# scrap.net
KiCad netlist of a schematic drawn in EAGLE
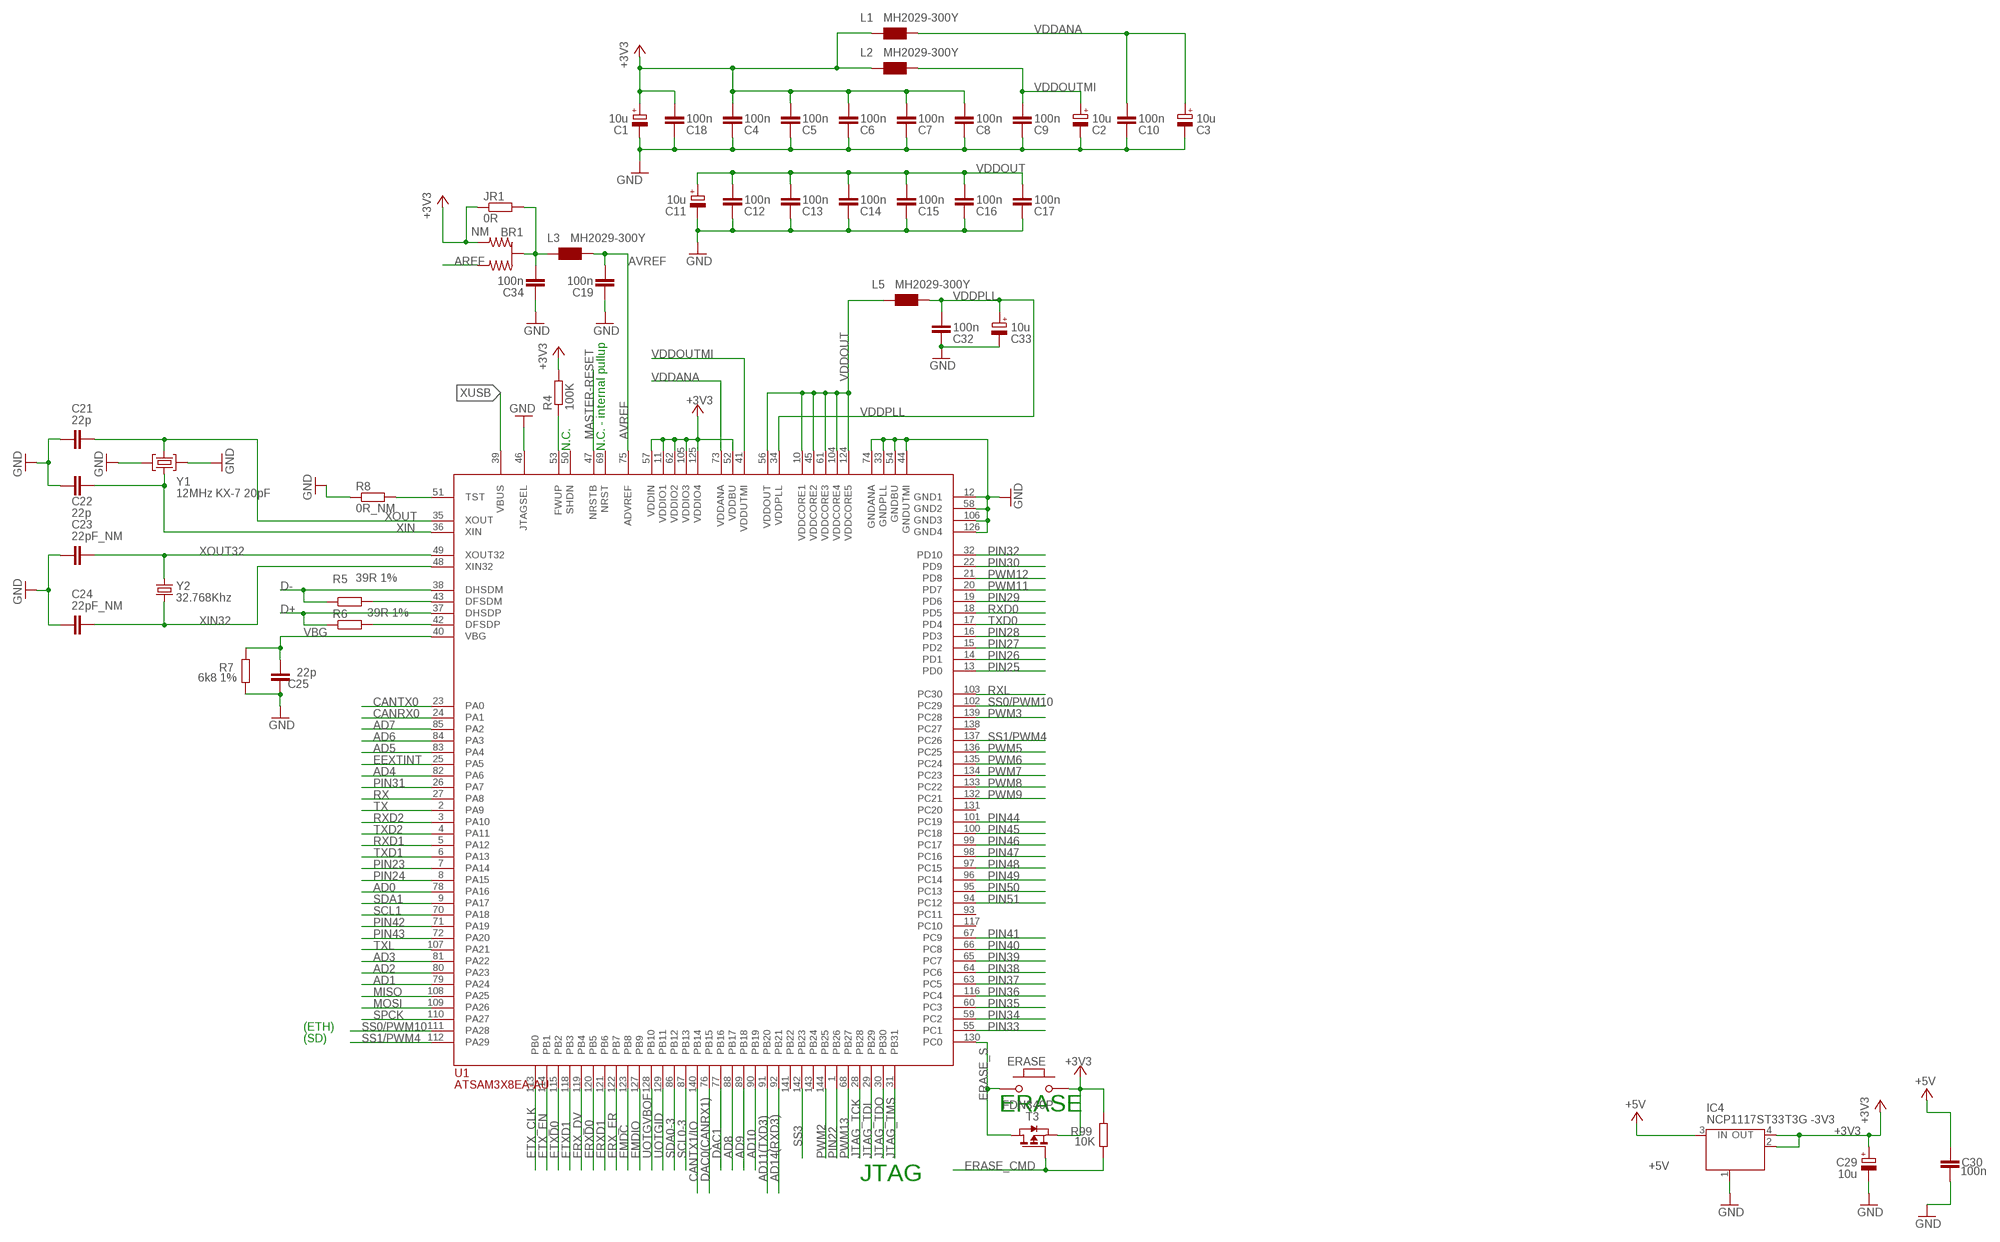
[diagram p0: schematic, sheet 1]

(export (version "E")
  (design (tool "Eeschema 10.0.6"))
  (components
    (comp (ref "BR1")
      (value "NM")
      (footprint "eagle-import:J0402")
      (libsource (lib "eagle-import") (part "J0402"))
    )
    (comp (ref "C1")
      (value "10u")
      (footprint "eagle-import:SMC_B")
      (libsource (lib "eagle-import") (part "CPOL-EUSMCB"))
    )
    (comp (ref "C2")
      (value "10u")
      (footprint "eagle-import:SMC_B")
      (libsource (lib "eagle-import") (part "CPOL-EUSMCB"))
    )
    (comp (ref "C3")
      (value "10u")
      (footprint "eagle-import:SMC_B")
      (libsource (lib "eagle-import") (part "CPOL-EUSMCB"))
    )
    (comp (ref "C4")
      (value "100n")
      (footprint "eagle-import:C0402")
      (libsource (lib "eagle-import") (part "C-EUC0402"))
    )
    (comp (ref "C5")
      (value "100n")
      (footprint "eagle-import:C0402")
      (libsource (lib "eagle-import") (part "C-EUC0402"))
    )
    (comp (ref "C6")
      (value "100n")
      (footprint "eagle-import:C0402")
      (libsource (lib "eagle-import") (part "C-EUC0402"))
    )
    (comp (ref "C7")
      (value "100n")
      (footprint "eagle-import:C0402")
      (libsource (lib "eagle-import") (part "C-EUC0402"))
    )
    (comp (ref "C8")
      (value "100n")
      (footprint "eagle-import:C0402")
      (libsource (lib "eagle-import") (part "C-EUC0402"))
    )
    (comp (ref "C9")
      (value "100n")
      (footprint "eagle-import:C0402")
      (libsource (lib "eagle-import") (part "C-EUC0402"))
    )
    (comp (ref "C10")
      (value "100n")
      (footprint "eagle-import:C0402")
      (libsource (lib "eagle-import") (part "C-EUC0402"))
    )
    (comp (ref "C11")
      (value "10u")
      (footprint "eagle-import:SMC_B")
      (libsource (lib "eagle-import") (part "CPOL-EUSMCB"))
    )
    (comp (ref "C12")
      (value "100n")
      (footprint "eagle-import:C0402")
      (libsource (lib "eagle-import") (part "C-EUC0402"))
    )
    (comp (ref "C13")
      (value "100n")
      (footprint "eagle-import:C0402")
      (libsource (lib "eagle-import") (part "C-EUC0402"))
    )
    (comp (ref "C14")
      (value "100n")
      (footprint "eagle-import:C0402")
      (libsource (lib "eagle-import") (part "C-EUC0402"))
    )
    (comp (ref "C15")
      (value "100n")
      (footprint "eagle-import:C0402")
      (libsource (lib "eagle-import") (part "C-EUC0402"))
    )
    (comp (ref "C16")
      (value "100n")
      (footprint "eagle-import:C0402")
      (libsource (lib "eagle-import") (part "C-EUC0402"))
    )
    (comp (ref "C17")
      (value "100n")
      (footprint "eagle-import:C0402")
      (libsource (lib "eagle-import") (part "C-EUC0402"))
    )
    (comp (ref "C18")
      (value "100n")
      (footprint "eagle-import:C0402")
      (libsource (lib "eagle-import") (part "C-EUC0402"))
    )
    (comp (ref "C19")
      (value "100n")
      (footprint "eagle-import:C0402")
      (libsource (lib "eagle-import") (part "C-EUC0402"))
    )
    (comp (ref "C21")
      (value "22p")
      (footprint "eagle-import:C0402")
      (libsource (lib "eagle-import") (part "C-EUC0402"))
    )
    (comp (ref "C22")
      (value "22p")
      (footprint "eagle-import:C0402")
      (libsource (lib "eagle-import") (part "C-EUC0402"))
    )
    (comp (ref "C23")
      (value "22pF_NM")
      (footprint "eagle-import:C0402")
      (libsource (lib "eagle-import") (part "C-EUC0402"))
    )
    (comp (ref "C24")
      (value "22pF_NM")
      (footprint "eagle-import:C0402")
      (libsource (lib "eagle-import") (part "C-EUC0402"))
    )
    (comp (ref "C25")
      (value "22p")
      (footprint "eagle-import:C0402")
      (libsource (lib "eagle-import") (part "C-EUC0402"))
    )
    (comp (ref "C29")
      (value "10u")
      (footprint "eagle-import:SMC_B")
      (libsource (lib "eagle-import") (part "CPOL-EUSMCB"))
    )
    (comp (ref "C30")
      (value "100n")
      (footprint "eagle-import:C0402")
      (libsource (lib "eagle-import") (part "C-EUC0402"))
    )
    (comp (ref "C32")
      (value "100n")
      (footprint "eagle-import:C0402")
      (libsource (lib "eagle-import") (part "C-EUC0402"))
    )
    (comp (ref "C33")
      (value "10u")
      (footprint "eagle-import:SMC_B")
      (libsource (lib "eagle-import") (part "CPOL-EUSMCB"))
    )
    (comp (ref "C34")
      (value "100n")
      (footprint "eagle-import:C0402")
      (libsource (lib "eagle-import") (part "C-EUC0402"))
    )
    (comp (ref "ERASE")
      (value "MYSMD_PB157")
      (footprint "eagle-import:SMD_157SW")
      (libsource (lib "eagle-import") (part "MYSMD_PB157"))
    )
    (comp (ref "IC4")
      (value "NCP1117ST33T3G -3V3")
      (footprint "eagle-import:SOT223")
      (libsource (lib "eagle-import") (part "MC33269ST-3.3T3"))
    )
    (comp (ref "JR1")
      (value "0R")
      (footprint "eagle-import:R0402")
      (libsource (lib "eagle-import") (part "R-EU_R0402"))
    )
    (comp (ref "L1")
      (value "MH2029-300Y")
      (footprint "eagle-import:0805")
      (libsource (lib "eagle-import") (part "WE-CBF_0805"))
    )
    (comp (ref "L2")
      (value "MH2029-300Y")
      (footprint "eagle-import:0805")
      (libsource (lib "eagle-import") (part "WE-CBF_0805"))
    )
    (comp (ref "L3")
      (value "MH2029-300Y")
      (footprint "eagle-import:0805")
      (libsource (lib "eagle-import") (part "WE-CBF_0805"))
    )
    (comp (ref "L5")
      (value "MH2029-300Y")
      (footprint "eagle-import:0805")
      (libsource (lib "eagle-import") (part "WE-CBF_0805"))
    )
    (comp (ref "R4")
      (value "100K")
      (footprint "eagle-import:R0402")
      (libsource (lib "eagle-import") (part "R-EU_R0402"))
    )
    (comp (ref "R5")
      (value "39R 1%")
      (footprint "eagle-import:R0402")
      (libsource (lib "eagle-import") (part "R-EU_R0402"))
    )
    (comp (ref "R6")
      (value "39R 1%")
      (footprint "eagle-import:R0402")
      (libsource (lib "eagle-import") (part "R-EU_R0402"))
    )
    (comp (ref "R7")
      (value "6k8 1%")
      (footprint "eagle-import:R0603-ROUND")
      (libsource (lib "eagle-import") (part "R-EU_R0603"))
    )
    (comp (ref "R8")
      (value "0R_NM")
      (footprint "eagle-import:R0402")
      (libsource (lib "eagle-import") (part "R-EU_R0402"))
    )
    (comp (ref "R99")
      (value "10K")
      (footprint "eagle-import:R0402")
      (libsource (lib "eagle-import") (part "R-EU_R0402"))
    )
    (comp (ref "T3")
      (value "FDN340P")
      (footprint "eagle-import:SOT-23")
      (libsource (lib "eagle-import") (part "PMOSSOT23"))
    )
    (comp (ref "U1")
      (value "ATSAM3X8EA-AU")
      (footprint "eagle-import:LQFP144")
      (libsource (lib "eagle-import") (part "ATSAM3X/AAU"))
    )
    (comp (ref "Y1")
      (value "12MHz KX-7 20pF")
      (footprint "eagle-import:CRYSTAL-3.2-2.5")
      (libsource (lib "eagle-import") (part "CRYSTAL-3.2-2.5"))
    )
    (comp (ref "Y2")
      (value "32.768Khz")
      (footprint "eagle-import:RESONATOR_EPSON_FC_145")
      (libsource (lib "eagle-import") (part "RESONATOR_EPSON_FC_145"))
    )
  )
  (nets
    (net (code "1") (name "+3V3") (class "Default")
      (node (ref "BR1") (pin "3") (pinfunction "2_3") (pintype "passive"))
      (node (ref "C1") (pin "+") (pinfunction "+_+") (pintype "passive"))
      (node (ref "C18") (pin "2") (pinfunction "2_2") (pintype "passive"))
      (node (ref "C29") (pin "+") (pinfunction "+_+") (pintype "passive"))
      (node (ref "C4") (pin "2") (pinfunction "2_2") (pintype "passive"))
      (node (ref "C5") (pin "2") (pinfunction "2_2") (pintype "passive"))
      (node (ref "C6") (pin "2") (pinfunction "2_2") (pintype "passive"))
      (node (ref "C7") (pin "2") (pinfunction "2_2") (pintype "passive"))
      (node (ref "C8") (pin "2") (pinfunction "2_2") (pintype "passive"))
      (node (ref "ERASE") (pin "1") (pinfunction "1_1") (pintype "passive"))
      (node (ref "IC4") (pin "2") (pinfunction "OUT_2") (pintype "passive"))
      (node (ref "IC4") (pin "4") (pinfunction "OUT_4") (pintype "passive"))
      (node (ref "JR1") (pin "1") (pinfunction "1_1") (pintype "passive"))
      (node (ref "L1") (pin "1") (pinfunction "1_1") (pintype "passive"))
      (node (ref "L2") (pin "1") (pinfunction "1_1") (pintype "passive"))
      (node (ref "R4") (pin "2") (pinfunction "2_2") (pintype "passive"))
      (node (ref "R99") (pin "2") (pinfunction "2_2") (pintype "passive"))
      (node (ref "T3") (pin "2") (pinfunction "S_2") (pintype "passive"))
      (node (ref "U1") (pin "105") (pinfunction "VDDIO3_105") (pintype "power_in"))
      (node (ref "U1") (pin "11") (pinfunction "VDDIO1_11") (pintype "power_in"))
      (node (ref "U1") (pin "125") (pinfunction "VDDIO4_125") (pintype "power_in"))
      (node (ref "U1") (pin "52") (pinfunction "VDDBU_52") (pintype "power_in"))
      (node (ref "U1") (pin "57") (pinfunction "VDDIN_57") (pintype "power_in"))
      (node (ref "U1") (pin "62") (pinfunction "VDDIO2_62") (pintype "power_in"))
    )
    (net (code "2") (name "+5V") (class "Default")
      (node (ref "C30") (pin "2") (pinfunction "2_2") (pintype "passive"))
      (node (ref "IC4") (pin "3") (pinfunction "IN_3") (pintype "input"))
    )
    (net (code "3") (name "/AD0") (class "Default")
      (node (ref "U1") (pin "78") (pinfunction "PA16_78") (pintype "bidirectional"))
    )
    (net (code "4") (name "/AD1") (class "Default")
      (node (ref "U1") (pin "79") (pinfunction "PA24_79") (pintype "bidirectional"))
    )
    (net (code "5") (name "/AD2") (class "Default")
      (node (ref "U1") (pin "80") (pinfunction "PA23_80") (pintype "bidirectional"))
    )
    (net (code "6") (name "/AD3") (class "Default")
      (node (ref "U1") (pin "81") (pinfunction "PA22_81") (pintype "bidirectional"))
    )
    (net (code "7") (name "/AD4") (class "Default")
      (node (ref "U1") (pin "82") (pinfunction "PA6_82") (pintype "bidirectional"))
    )
    (net (code "8") (name "/AD5") (class "Default")
      (node (ref "U1") (pin "83") (pinfunction "PA4_83") (pintype "bidirectional"))
    )
    (net (code "9") (name "/AD6") (class "Default")
      (node (ref "U1") (pin "84") (pinfunction "PA3_84") (pintype "bidirectional"))
    )
    (net (code "10") (name "/AD7") (class "Default")
      (node (ref "U1") (pin "85") (pinfunction "PA2_85") (pintype "bidirectional"))
    )
    (net (code "11") (name "/AD8") (class "Default")
      (node (ref "U1") (pin "88") (pinfunction "PB17_88") (pintype "bidirectional"))
    )
    (net (code "12") (name "/AD9") (class "Default")
      (node (ref "U1") (pin "89") (pinfunction "PB18_89") (pintype "bidirectional"))
    )
    (net (code "13") (name "/AD10") (class "Default")
      (node (ref "U1") (pin "90") (pinfunction "PB19_90") (pintype "bidirectional"))
    )
    (net (code "14") (name "/AD11(TXD3)") (class "Default")
      (node (ref "U1") (pin "91") (pinfunction "PB20_91") (pintype "bidirectional"))
    )
    (net (code "15") (name "/AD14(RXD3)") (class "Default")
      (node (ref "U1") (pin "92") (pinfunction "PB21_92") (pintype "bidirectional"))
    )
    (net (code "16") (name "/AREF") (class "Default")
      (node (ref "BR1") (pin "1") (pinfunction "1_1") (pintype "passive"))
    )
    (net (code "17") (name "/AVREF") (class "Default")
      (node (ref "C19") (pin "2") (pinfunction "2_2") (pintype "passive"))
      (node (ref "L3") (pin "2") (pinfunction "2_2") (pintype "passive"))
      (node (ref "U1") (pin "75") (pinfunction "ADVREF_75") (pintype "power_in"))
    )
    (net (code "18") (name "/CANRX0") (class "Default")
      (node (ref "U1") (pin "24") (pinfunction "PA1_24") (pintype "bidirectional"))
    )
    (net (code "19") (name "/CANTX0") (class "Default")
      (node (ref "U1") (pin "23") (pinfunction "PA0_23") (pintype "bidirectional"))
    )
    (net (code "20") (name "/CANTX1{slash}IO") (class "Default")
      (node (ref "U1") (pin "140") (pinfunction "PB14_140") (pintype "bidirectional"))
    )
    (net (code "21") (name "/D+") (class "Default")
      (node (ref "R6") (pin "1") (pinfunction "1_1") (pintype "passive"))
      (node (ref "U1") (pin "37") (pinfunction "DHSDP_37") (pintype "bidirectional"))
    )
    (net (code "22") (name "/D-") (class "Default")
      (node (ref "R5") (pin "1") (pinfunction "1_1") (pintype "passive"))
      (node (ref "U1") (pin "38") (pinfunction "DHSDM_38") (pintype "bidirectional"))
    )
    (net (code "23") (name "/DAC0(CANRX1)") (class "Default")
      (node (ref "U1") (pin "76") (pinfunction "PB15_76") (pintype "bidirectional"))
    )
    (net (code "24") (name "/DAC1") (class "Default")
      (node (ref "U1") (pin "77") (pinfunction "PB16_77") (pintype "bidirectional"))
    )
    (net (code "25") (name "/EEXTINT") (class "Default")
      (node (ref "U1") (pin "25") (pinfunction "PA5_25") (pintype "bidirectional"))
    )
    (net (code "26") (name "/EMDC") (class "Default")
      (node (ref "U1") (pin "123") (pinfunction "PB8_123") (pintype "bidirectional"))
    )
    (net (code "27") (name "/EMDIO") (class "Default")
      (node (ref "U1") (pin "127") (pinfunction "PB9_127") (pintype "bidirectional"))
    )
    (net (code "28") (name "/ERASE_CMD") (class "Default")
      (node (ref "R99") (pin "1") (pinfunction "1_1") (pintype "passive"))
      (node (ref "T3") (pin "3") (pinfunction "G_3") (pintype "passive"))
    )
    (net (code "29") (name "/ERASE_S") (class "Default")
      (node (ref "ERASE") (pin "2") (pinfunction "2_2") (pintype "passive"))
      (node (ref "T3") (pin "1") (pinfunction "D_1") (pintype "passive"))
      (node (ref "U1") (pin "130") (pinfunction "PC0_130") (pintype "bidirectional"))
    )
    (net (code "30") (name "/ERXD0") (class "Default")
      (node (ref "U1") (pin "120") (pinfunction "PB5_120") (pintype "bidirectional"))
    )
    (net (code "31") (name "/ERXD1") (class "Default")
      (node (ref "U1") (pin "121") (pinfunction "PB6_121") (pintype "bidirectional"))
    )
    (net (code "32") (name "/ERX_DV") (class "Default")
      (node (ref "U1") (pin "119") (pinfunction "PB4_119") (pintype "bidirectional"))
    )
    (net (code "33") (name "/ERX_ER") (class "Default")
      (node (ref "U1") (pin "122") (pinfunction "PB7_122") (pintype "bidirectional"))
    )
    (net (code "34") (name "/ETXD0") (class "Default")
      (node (ref "U1") (pin "115") (pinfunction "PB2_115") (pintype "bidirectional"))
    )
    (net (code "35") (name "/ETXD1") (class "Default")
      (node (ref "U1") (pin "118") (pinfunction "PB3_118") (pintype "bidirectional"))
    )
    (net (code "36") (name "/ETX_CLK") (class "Default")
      (node (ref "U1") (pin "113") (pinfunction "PB0_113") (pintype "bidirectional"))
    )
    (net (code "37") (name "/ETX_EN") (class "Default")
      (node (ref "U1") (pin "114") (pinfunction "PB1_114") (pintype "bidirectional"))
    )
    (net (code "38") (name "/JTAG_TCK") (class "Default")
      (node (ref "U1") (pin "28") (pinfunction "PB28_28") (pintype "bidirectional"))
    )
    (net (code "39") (name "/JTAG_TDI") (class "Default")
      (node (ref "U1") (pin "29") (pinfunction "PB29_29") (pintype "bidirectional"))
    )
    (net (code "40") (name "/JTAG_TDO") (class "Default")
      (node (ref "U1") (pin "30") (pinfunction "PB30_30") (pintype "bidirectional"))
    )
    (net (code "41") (name "/JTAG_TMS") (class "Default")
      (node (ref "U1") (pin "31") (pinfunction "PB31_31") (pintype "bidirectional"))
    )
    (net (code "42") (name "/MASTER-RESET") (class "Default")
      (node (ref "U1") (pin "47") (pinfunction "NRSTB_47") (pintype "input"))
    )
    (net (code "43") (name "/MISO") (class "Default")
      (node (ref "U1") (pin "108") (pinfunction "PA25_108") (pintype "bidirectional"))
    )
    (net (code "44") (name "/MOSI") (class "Default")
      (node (ref "U1") (pin "109") (pinfunction "PA26_109") (pintype "bidirectional"))
    )
    (net (code "45") (name "/PIN22") (class "Default")
      (node (ref "U1") (pin "1") (pinfunction "PB26_1") (pintype "bidirectional"))
    )
    (net (code "46") (name "/PIN23") (class "Default")
      (node (ref "U1") (pin "7") (pinfunction "PA14_7") (pintype "bidirectional"))
    )
    (net (code "47") (name "/PIN24") (class "Default")
      (node (ref "U1") (pin "8") (pinfunction "PA15_8") (pintype "bidirectional"))
    )
    (net (code "48") (name "/PIN25") (class "Default")
      (node (ref "U1") (pin "13") (pinfunction "PD0_13") (pintype "bidirectional"))
    )
    (net (code "49") (name "/PIN26") (class "Default")
      (node (ref "U1") (pin "14") (pinfunction "PD1_14") (pintype "bidirectional"))
    )
    (net (code "50") (name "/PIN27") (class "Default")
      (node (ref "U1") (pin "15") (pinfunction "PD2_15") (pintype "bidirectional"))
    )
    (net (code "51") (name "/PIN28") (class "Default")
      (node (ref "U1") (pin "16") (pinfunction "PD3_16") (pintype "bidirectional"))
    )
    (net (code "52") (name "/PIN29") (class "Default")
      (node (ref "U1") (pin "19") (pinfunction "PD6_19") (pintype "bidirectional"))
    )
    (net (code "53") (name "/PIN30") (class "Default")
      (node (ref "U1") (pin "22") (pinfunction "PD9_22") (pintype "bidirectional"))
    )
    (net (code "54") (name "/PIN31") (class "Default")
      (node (ref "U1") (pin "26") (pinfunction "PA7_26") (pintype "bidirectional"))
    )
    (net (code "55") (name "/PIN32") (class "Default")
      (node (ref "U1") (pin "32") (pinfunction "PD10_32") (pintype "bidirectional"))
    )
    (net (code "56") (name "/PIN33") (class "Default")
      (node (ref "U1") (pin "55") (pinfunction "PC1_55") (pintype "bidirectional"))
    )
    (net (code "57") (name "/PIN34") (class "Default")
      (node (ref "U1") (pin "59") (pinfunction "PC2_59") (pintype "bidirectional"))
    )
    (net (code "58") (name "/PIN35") (class "Default")
      (node (ref "U1") (pin "60") (pinfunction "PC3_60") (pintype "bidirectional"))
    )
    (net (code "59") (name "/PIN36") (class "Default")
      (node (ref "U1") (pin "116") (pinfunction "PC4_116") (pintype "bidirectional"))
    )
    (net (code "60") (name "/PIN37") (class "Default")
      (node (ref "U1") (pin "63") (pinfunction "PC5_63") (pintype "bidirectional"))
    )
    (net (code "61") (name "/PIN38") (class "Default")
      (node (ref "U1") (pin "64") (pinfunction "PC6_64") (pintype "bidirectional"))
    )
    (net (code "62") (name "/PIN39") (class "Default")
      (node (ref "U1") (pin "65") (pinfunction "PC7_65") (pintype "bidirectional"))
    )
    (net (code "63") (name "/PIN40") (class "Default")
      (node (ref "U1") (pin "66") (pinfunction "PC8_66") (pintype "bidirectional"))
    )
    (net (code "64") (name "/PIN41") (class "Default")
      (node (ref "U1") (pin "67") (pinfunction "PC9_67") (pintype "bidirectional"))
    )
    (net (code "65") (name "/PIN42") (class "Default")
      (node (ref "U1") (pin "71") (pinfunction "PA19_71") (pintype "bidirectional"))
    )
    (net (code "66") (name "/PIN43") (class "Default")
      (node (ref "U1") (pin "72") (pinfunction "PA20_72") (pintype "bidirectional"))
    )
    (net (code "67") (name "/PIN44") (class "Default")
      (node (ref "U1") (pin "101") (pinfunction "PC19_101") (pintype "bidirectional"))
    )
    (net (code "68") (name "/PIN45") (class "Default")
      (node (ref "U1") (pin "100") (pinfunction "PC18_100") (pintype "bidirectional"))
    )
    (net (code "69") (name "/PIN46") (class "Default")
      (node (ref "U1") (pin "99") (pinfunction "PC17_99") (pintype "bidirectional"))
    )
    (net (code "70") (name "/PIN47") (class "Default")
      (node (ref "U1") (pin "98") (pinfunction "PC16_98") (pintype "bidirectional"))
    )
    (net (code "71") (name "/PIN48") (class "Default")
      (node (ref "U1") (pin "97") (pinfunction "PC15_97") (pintype "bidirectional"))
    )
    (net (code "72") (name "/PIN49") (class "Default")
      (node (ref "U1") (pin "96") (pinfunction "PC14_96") (pintype "bidirectional"))
    )
    (net (code "73") (name "/PIN50") (class "Default")
      (node (ref "U1") (pin "95") (pinfunction "PC13_95") (pintype "bidirectional"))
    )
    (net (code "74") (name "/PIN51") (class "Default")
      (node (ref "U1") (pin "94") (pinfunction "PC12_94") (pintype "bidirectional"))
    )
    (net (code "75") (name "/PWM2") (class "Default")
      (node (ref "U1") (pin "144") (pinfunction "PB25_144") (pintype "bidirectional"))
    )
    (net (code "76") (name "/PWM3") (class "Default")
      (node (ref "U1") (pin "139") (pinfunction "PC28_139") (pintype "bidirectional"))
    )
    (net (code "77") (name "/PWM5") (class "Default")
      (node (ref "U1") (pin "136") (pinfunction "PC25_136") (pintype "bidirectional"))
    )
    (net (code "78") (name "/PWM6") (class "Default")
      (node (ref "U1") (pin "135") (pinfunction "PC24_135") (pintype "bidirectional"))
    )
    (net (code "79") (name "/PWM7") (class "Default")
      (node (ref "U1") (pin "134") (pinfunction "PC23_134") (pintype "bidirectional"))
    )
    (net (code "80") (name "/PWM8") (class "Default")
      (node (ref "U1") (pin "133") (pinfunction "PC22_133") (pintype "bidirectional"))
    )
    (net (code "81") (name "/PWM9") (class "Default")
      (node (ref "U1") (pin "132") (pinfunction "PC21_132") (pintype "bidirectional"))
    )
    (net (code "82") (name "/PWM11") (class "Default")
      (node (ref "U1") (pin "20") (pinfunction "PD7_20") (pintype "bidirectional"))
    )
    (net (code "83") (name "/PWM12") (class "Default")
      (node (ref "U1") (pin "21") (pinfunction "PD8_21") (pintype "bidirectional"))
    )
    (net (code "84") (name "/PWM13") (class "Default")
      (node (ref "U1") (pin "68") (pinfunction "PB27_68") (pintype "bidirectional"))
    )
    (net (code "85") (name "/RX") (class "Default")
      (node (ref "U1") (pin "27") (pinfunction "PA8_27") (pintype "bidirectional"))
    )
    (net (code "86") (name "/RXD0") (class "Default")
      (node (ref "U1") (pin "18") (pinfunction "PD5_18") (pintype "bidirectional"))
    )
    (net (code "87") (name "/RXD1") (class "Default")
      (node (ref "U1") (pin "5") (pinfunction "PA12_5") (pintype "bidirectional"))
    )
    (net (code "88") (name "/RXD2") (class "Default")
      (node (ref "U1") (pin "3") (pinfunction "PA10_3") (pintype "bidirectional"))
    )
    (net (code "89") (name "/RXL") (class "Default")
      (node (ref "U1") (pin "103") (pinfunction "PC30_103") (pintype "bidirectional"))
    )
    (net (code "90") (name "/SCL0-3") (class "Default")
      (node (ref "U1") (pin "87") (pinfunction "PB13_87") (pintype "bidirectional"))
    )
    (net (code "91") (name "/SCL1") (class "Default")
      (node (ref "U1") (pin "70") (pinfunction "PA18_70") (pintype "bidirectional"))
    )
    (net (code "92") (name "/SDA0-3") (class "Default")
      (node (ref "U1") (pin "86") (pinfunction "PB12_86") (pintype "bidirectional"))
    )
    (net (code "93") (name "/SDA1") (class "Default")
      (node (ref "U1") (pin "9") (pinfunction "PA17_9") (pintype "bidirectional"))
    )
    (net (code "94") (name "/SPCK") (class "Default")
      (node (ref "U1") (pin "110") (pinfunction "PA27_110") (pintype "bidirectional"))
    )
    (net (code "95") (name "/SS0{slash}PWM10") (class "Default")
      (node (ref "U1") (pin "102") (pinfunction "PC29_102") (pintype "bidirectional"))
      (node (ref "U1") (pin "111") (pinfunction "PA28_111") (pintype "bidirectional"))
    )
    (net (code "96") (name "/SS1{slash}PWM4") (class "Default")
      (node (ref "U1") (pin "112") (pinfunction "PA29_112") (pintype "bidirectional"))
      (node (ref "U1") (pin "137") (pinfunction "PC26_137") (pintype "bidirectional"))
    )
    (net (code "97") (name "/SS3") (class "Default")
      (node (ref "U1") (pin "142") (pinfunction "PB23_142") (pintype "bidirectional"))
    )
    (net (code "98") (name "/TX") (class "Default")
      (node (ref "U1") (pin "2") (pinfunction "PA9_2") (pintype "bidirectional"))
    )
    (net (code "99") (name "/TXD0") (class "Default")
      (node (ref "U1") (pin "17") (pinfunction "PD4_17") (pintype "bidirectional"))
    )
    (net (code "100") (name "/TXD1") (class "Default")
      (node (ref "U1") (pin "6") (pinfunction "PA13_6") (pintype "bidirectional"))
    )
    (net (code "101") (name "/TXD2") (class "Default")
      (node (ref "U1") (pin "4") (pinfunction "PA11_4") (pintype "bidirectional"))
    )
    (net (code "102") (name "/TXL") (class "Default")
      (node (ref "U1") (pin "107") (pinfunction "PA21_107") (pintype "bidirectional"))
    )
    (net (code "103") (name "/UOTGID") (class "Default")
      (node (ref "U1") (pin "129") (pinfunction "PB11_129") (pintype "bidirectional"))
    )
    (net (code "104") (name "/UOTGVBOF") (class "Default")
      (node (ref "U1") (pin "128") (pinfunction "PB10_128") (pintype "bidirectional"))
    )
    (net (code "105") (name "/VBG") (class "Default")
      (node (ref "C25") (pin "1") (pinfunction "1_1") (pintype "passive"))
      (node (ref "R7") (pin "2") (pinfunction "2_2") (pintype "passive"))
      (node (ref "U1") (pin "40") (pinfunction "VBG_40") (pintype "passive"))
    )
    (net (code "106") (name "/VDDANA") (class "Default")
      (node (ref "C10") (pin "2") (pinfunction "2_2") (pintype "passive"))
      (node (ref "C3") (pin "+") (pinfunction "+_+") (pintype "passive"))
      (node (ref "L1") (pin "2") (pinfunction "2_2") (pintype "passive"))
      (node (ref "U1") (pin "73") (pinfunction "VDDANA_73") (pintype "power_in"))
    )
    (net (code "107") (name "/VDDOUT") (class "Default")
      (node (ref "C11") (pin "+") (pinfunction "+_+") (pintype "passive"))
      (node (ref "C12") (pin "2") (pinfunction "2_2") (pintype "passive"))
      (node (ref "C13") (pin "2") (pinfunction "2_2") (pintype "passive"))
      (node (ref "C14") (pin "2") (pinfunction "2_2") (pintype "passive"))
      (node (ref "C15") (pin "2") (pinfunction "2_2") (pintype "passive"))
      (node (ref "C16") (pin "2") (pinfunction "2_2") (pintype "passive"))
      (node (ref "C17") (pin "2") (pinfunction "2_2") (pintype "passive"))
      (node (ref "L5") (pin "1") (pinfunction "1_1") (pintype "passive"))
      (node (ref "U1") (pin "10") (pinfunction "VDDCORE1_10") (pintype "input"))
      (node (ref "U1") (pin "104") (pinfunction "VDDCORE4_104") (pintype "input"))
      (node (ref "U1") (pin "124") (pinfunction "VDDCORE5_124") (pintype "input"))
      (node (ref "U1") (pin "45") (pinfunction "VDDCORE2_45") (pintype "input"))
      (node (ref "U1") (pin "56") (pinfunction "VDDOUT_56") (pintype "output"))
      (node (ref "U1") (pin "61") (pinfunction "VDDCORE3_61") (pintype "input"))
    )
    (net (code "108") (name "/VDDOUTMI") (class "Default")
      (node (ref "C2") (pin "+") (pinfunction "+_+") (pintype "passive"))
      (node (ref "C9") (pin "2") (pinfunction "2_2") (pintype "passive"))
      (node (ref "L2") (pin "2") (pinfunction "2_2") (pintype "passive"))
      (node (ref "U1") (pin "41") (pinfunction "VDDUTMI_41") (pintype "input"))
    )
    (net (code "109") (name "/VDDPLL") (class "Default")
      (node (ref "C32") (pin "2") (pinfunction "2_2") (pintype "passive"))
      (node (ref "C33") (pin "+") (pinfunction "+_+") (pintype "passive"))
      (node (ref "L5") (pin "2") (pinfunction "2_2") (pintype "passive"))
      (node (ref "U1") (pin "34") (pinfunction "VDDPLL_34") (pintype "input"))
    )
    (net (code "110") (name "/XIN") (class "Default")
      (node (ref "C22") (pin "1") (pinfunction "1_1") (pintype "passive"))
      (node (ref "U1") (pin "36") (pinfunction "XIN_36") (pintype "input"))
      (node (ref "Y1") (pin "1") (pinfunction "C1_1") (pintype "passive"))
    )
    (net (code "111") (name "/XIN32") (class "Default")
      (node (ref "C24") (pin "1") (pinfunction "1_1") (pintype "passive"))
      (node (ref "U1") (pin "48") (pinfunction "XIN32_48") (pintype "output"))
      (node (ref "Y2") (pin "P$2") (pinfunction "2_P$2") (pintype "bidirectional"))
    )
    (net (code "112") (name "/XOUT") (class "Default")
      (node (ref "C21") (pin "1") (pinfunction "1_1") (pintype "passive"))
      (node (ref "U1") (pin "35") (pinfunction "XOUT_35") (pintype "output"))
      (node (ref "Y1") (pin "3") (pinfunction "C2_3") (pintype "passive"))
    )
    (net (code "113") (name "/XOUT32") (class "Default")
      (node (ref "C23") (pin "1") (pinfunction "1_1") (pintype "passive"))
      (node (ref "U1") (pin "49") (pinfunction "XOUT32_49") (pintype "output"))
      (node (ref "Y2") (pin "P$1") (pinfunction "1_P$1") (pintype "bidirectional"))
    )
    (net (code "114") (name "GND") (class "Default")
      (node (ref "C1") (pin "-") (pinfunction "-_-") (pintype "passive"))
      (node (ref "C10") (pin "1") (pinfunction "1_1") (pintype "passive"))
      (node (ref "C11") (pin "-") (pinfunction "-_-") (pintype "passive"))
      (node (ref "C12") (pin "1") (pinfunction "1_1") (pintype "passive"))
      (node (ref "C13") (pin "1") (pinfunction "1_1") (pintype "passive"))
      (node (ref "C14") (pin "1") (pinfunction "1_1") (pintype "passive"))
      (node (ref "C15") (pin "1") (pinfunction "1_1") (pintype "passive"))
      (node (ref "C16") (pin "1") (pinfunction "1_1") (pintype "passive"))
      (node (ref "C17") (pin "1") (pinfunction "1_1") (pintype "passive"))
      (node (ref "C18") (pin "1") (pinfunction "1_1") (pintype "passive"))
      (node (ref "C19") (pin "1") (pinfunction "1_1") (pintype "passive"))
      (node (ref "C2") (pin "-") (pinfunction "-_-") (pintype "passive"))
      (node (ref "C21") (pin "2") (pinfunction "2_2") (pintype "passive"))
      (node (ref "C22") (pin "2") (pinfunction "2_2") (pintype "passive"))
      (node (ref "C23") (pin "2") (pinfunction "2_2") (pintype "passive"))
      (node (ref "C24") (pin "2") (pinfunction "2_2") (pintype "passive"))
      (node (ref "C25") (pin "2") (pinfunction "2_2") (pintype "passive"))
      (node (ref "C29") (pin "-") (pinfunction "-_-") (pintype "passive"))
      (node (ref "C3") (pin "-") (pinfunction "-_-") (pintype "passive"))
      (node (ref "C30") (pin "1") (pinfunction "1_1") (pintype "passive"))
      (node (ref "C32") (pin "1") (pinfunction "1_1") (pintype "passive"))
      (node (ref "C33") (pin "-") (pinfunction "-_-") (pintype "passive"))
      (node (ref "C34") (pin "1") (pinfunction "1_1") (pintype "passive"))
      (node (ref "C4") (pin "1") (pinfunction "1_1") (pintype "passive"))
      (node (ref "C5") (pin "1") (pinfunction "1_1") (pintype "passive"))
      (node (ref "C6") (pin "1") (pinfunction "1_1") (pintype "passive"))
      (node (ref "C7") (pin "1") (pinfunction "1_1") (pintype "passive"))
      (node (ref "C8") (pin "1") (pinfunction "1_1") (pintype "passive"))
      (node (ref "C9") (pin "1") (pinfunction "1_1") (pintype "passive"))
      (node (ref "IC4") (pin "1") (pinfunction "GND/ADJ_1") (pintype "input"))
      (node (ref "R7") (pin "1") (pinfunction "1_1") (pintype "passive"))
      (node (ref "R8") (pin "1") (pinfunction "1_1") (pintype "passive"))
      (node (ref "U1") (pin "106") (pinfunction "GND3_106") (pintype "power_in"))
      (node (ref "U1") (pin "12") (pinfunction "GND1_12") (pintype "power_in"))
      (node (ref "U1") (pin "126") (pinfunction "GND4_126") (pintype "power_in"))
      (node (ref "U1") (pin "33") (pinfunction "GNDPLL_33") (pintype "power_in"))
      (node (ref "U1") (pin "44") (pinfunction "GNDUTMI_44") (pintype "power_in"))
      (node (ref "U1") (pin "46") (pinfunction "JTAGSEL_46") (pintype "input"))
      (node (ref "U1") (pin "54") (pinfunction "GNDBU_54") (pintype "power_in"))
      (node (ref "U1") (pin "58") (pinfunction "GND2_58") (pintype "power_in"))
      (node (ref "U1") (pin "74") (pinfunction "GNDANA_74") (pintype "power_in"))
      (node (ref "Y1") (pin "2") (pinfunction "GND_2") (pintype "passive"))
      (node (ref "Y1") (pin "4") (pinfunction "GND_4") (pintype "passive"))
    )
    (net (code "115") (name "Net-(BR1-C)") (class "Default")
      (node (ref "BR1") (pin "2") (pinfunction "C_2") (pintype "passive"))
      (node (ref "C34") (pin "2") (pinfunction "2_2") (pintype "passive"))
      (node (ref "JR1") (pin "2") (pinfunction "2_2") (pintype "passive"))
      (node (ref "L3") (pin "1") (pinfunction "1_1") (pintype "passive"))
    )
    (net (code "116") (name "Net-(U1-DFSDM)") (class "Default")
      (node (ref "R5") (pin "2") (pinfunction "2_2") (pintype "passive"))
      (node (ref "U1") (pin "43") (pinfunction "DFSDM_43") (pintype "input"))
    )
    (net (code "117") (name "Net-(U1-DFSDP)") (class "Default")
      (node (ref "R6") (pin "2") (pinfunction "2_2") (pintype "passive"))
      (node (ref "U1") (pin "42") (pinfunction "DFSDP_42") (pintype "input"))
    )
    (net (code "118") (name "Net-(U1-FWUP)") (class "Default")
      (node (ref "R4") (pin "1") (pinfunction "1_1") (pintype "passive"))
      (node (ref "U1") (pin "53") (pinfunction "FWUP_53") (pintype "input"))
    )
    (net (code "119") (name "Net-(U1-TST)") (class "Default")
      (node (ref "R8") (pin "2") (pinfunction "2_2") (pintype "passive"))
      (node (ref "U1") (pin "51") (pinfunction "TST_51") (pintype "input"))
    )
    (net (code "120") (name "XUSB") (class "Default")
      (node (ref "U1") (pin "39") (pinfunction "VBUS_39") (pintype "power_in"))
    )
    (net (code "121") (name "unconnected-(U1-NRST-Pad69)") (class "Default")
      (node (ref "U1") (pin "69") (pinfunction "NRST_69") (pintype "bidirectional"))
    )
    (net (code "122") (name "unconnected-(U1-PB22-Pad141)") (class "Default")
      (node (ref "U1") (pin "141") (pinfunction "PB22_141") (pintype "bidirectional"))
    )
    (net (code "123") (name "unconnected-(U1-PB24-Pad143)") (class "Default")
      (node (ref "U1") (pin "143") (pinfunction "PB24_143") (pintype "bidirectional"))
    )
    (net (code "124") (name "unconnected-(U1-PC10-Pad117)") (class "Default")
      (node (ref "U1") (pin "117") (pinfunction "PC10_117") (pintype "bidirectional"))
    )
    (net (code "125") (name "unconnected-(U1-PC11-Pad93)") (class "Default")
      (node (ref "U1") (pin "93") (pinfunction "PC11_93") (pintype "bidirectional"))
    )
    (net (code "126") (name "unconnected-(U1-PC20-Pad131)") (class "Default")
      (node (ref "U1") (pin "131") (pinfunction "PC20_131") (pintype "bidirectional"))
    )
    (net (code "127") (name "unconnected-(U1-PC27-Pad138)") (class "Default")
      (node (ref "U1") (pin "138") (pinfunction "PC27_138") (pintype "bidirectional"))
    )
    (net (code "128") (name "unconnected-(U1-SHDN-Pad50)") (class "Default")
      (node (ref "U1") (pin "50") (pinfunction "SHDN_50") (pintype "output"))
    )
  )
)
